# CamBienGiaToc.net
KiCad netlist of a schematic drawn in Altium Designer
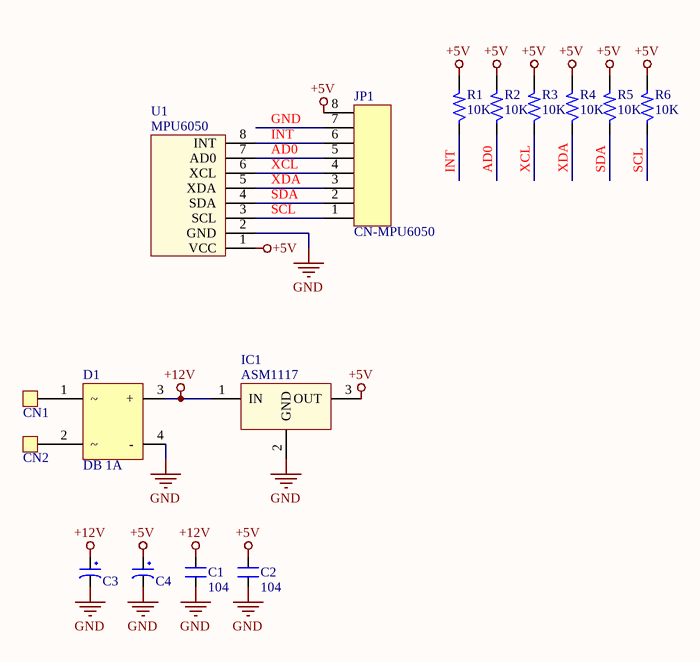
[diagram p0: CamBienGiaToc.SchDoc]

(export (version "E")
  (design (tool "Eeschema 10.0.6"))
  (components
    (comp (ref "C1")
      (value "104")
      (footprint "C-0805")
      (fields (field (name "DESIGNED BY") "VanDungEvn"))
      (libsource (lib "syhaunguyen") (part "CN"))
    )
    (comp (ref "C2")
      (value "104")
      (footprint "C-0805")
      (fields (field (name "DESIGNED BY") "VanDungEvn"))
      (libsource (lib "syhaunguyen") (part "CN"))
    )
    (comp (ref "C3")
      (value "10uF")
      (footprint "C-TANT-7343-31-CASEA")
      (description "Cap P  0,1uF < 22uF , 16 - 50V")
      (libsource (lib "syhaunguyen") (part "CP1"))
    )
    (comp (ref "C4")
      (value "10uF")
      (footprint "C-TANT-7343-31-CASEA")
      (description "Cap P  0,1uF < 22uF , 16 - 50V")
      (libsource (lib "syhaunguyen") (part "CP1"))
    )
    (comp (ref "CN1")
      (value "COCDONGM3")
      (footprint "M3")
      (libsource (lib "doAnTotNghiep2017Lib") (part "COCDONGM3"))
    )
    (comp (ref "CN2")
      (value "COCDONGM3")
      (footprint "M3")
      (libsource (lib "doAnTotNghiep2017Lib") (part "COCDONGM3"))
    )
    (comp (ref "D1")
      (value "DB 1A")
      (footprint "D-DB-1A-SMD")
      (libsource (lib "doAnTotNghiep2017Lib") (part "DB"))
    )
    (comp (ref "IC1")
      (value "ASM1117")
      (footprint "TO-252")
      (description "On ap +, from + 5 to + 24VDC")
      (libsource (lib "syhaunguyen") (part "LM78xx"))
    )
    (comp (ref "JP1")
      (value "CN-MPU6050")
      (footprint "JP8")
      (libsource (lib "doAnTotNghiep2017Lib") (part "JP8"))
    )
    (comp (ref "R1")
      (value "10K")
      (footprint "R-0805")
      (description "Resistor 1/4W")
      (libsource (lib "syhaunguyen") (part "R"))
    )
    (comp (ref "R2")
      (value "10K")
      (footprint "R-0805")
      (description "Resistor 1/4W")
      (libsource (lib "syhaunguyen") (part "R"))
    )
    (comp (ref "R3")
      (value "10K")
      (footprint "R-0805")
      (description "Resistor 1/4W")
      (libsource (lib "syhaunguyen") (part "R"))
    )
    (comp (ref "R4")
      (value "10K")
      (footprint "R-0805")
      (description "Resistor 1/4W")
      (libsource (lib "syhaunguyen") (part "R"))
    )
    (comp (ref "R5")
      (value "10K")
      (footprint "R-0805")
      (description "Resistor 1/4W")
      (libsource (lib "syhaunguyen") (part "R"))
    )
    (comp (ref "R6")
      (value "10K")
      (footprint "R-0805")
      (description "Resistor 1/4W")
      (libsource (lib "syhaunguyen") (part "R"))
    )
    (comp (ref "U1") (value "MPU6050") (libsource (lib "doAnTotNghiep2017Lib") (part "MPU6050")))
  )
  (nets
    (net (code "1") (name "+5V") (class "Default")
      (node (ref "C2") (pin "2") (pinfunction "2_2") (pintype "passive"))
      (node (ref "C4") (pin "1") (pinfunction "1_1") (pintype "passive"))
      (node (ref "IC1") (pin "3") (pinfunction "OUT_3") (pintype "passive"))
      (node (ref "JP1") (pin "8") (pinfunction "8_8") (pintype "passive"))
      (node (ref "R1") (pin "2") (pinfunction "2_2") (pintype "passive"))
      (node (ref "R2") (pin "2") (pinfunction "2_2") (pintype "passive"))
      (node (ref "R3") (pin "2") (pinfunction "2_2") (pintype "passive"))
      (node (ref "R4") (pin "2") (pinfunction "2_2") (pintype "passive"))
      (node (ref "R5") (pin "2") (pinfunction "2_2") (pintype "passive"))
      (node (ref "R6") (pin "2") (pinfunction "2_2") (pintype "passive"))
      (node (ref "U1") (pin "1") (pinfunction "VCC_1") (pintype "passive"))
    )
    (net (code "2") (name "+12V") (class "Default")
      (node (ref "C1") (pin "2") (pinfunction "2_2") (pintype "passive"))
      (node (ref "C3") (pin "1") (pinfunction "1_1") (pintype "passive"))
      (node (ref "D1") (pin "3") (pinfunction "+_3") (pintype "passive"))
      (node (ref "IC1") (pin "1") (pinfunction "IN_1") (pintype "passive"))
    )
    (net (code "3") (name "/AD0") (class "Default")
      (node (ref "JP1") (pin "5") (pinfunction "5_5") (pintype "passive"))
      (node (ref "R2") (pin "1") (pinfunction "1_1") (pintype "passive"))
      (node (ref "U1") (pin "7") (pinfunction "AD0_7") (pintype "passive"))
    )
    (net (code "4") (name "/INT") (class "Default")
      (node (ref "JP1") (pin "6") (pinfunction "6_6") (pintype "passive"))
      (node (ref "R1") (pin "1") (pinfunction "1_1") (pintype "passive"))
      (node (ref "U1") (pin "8") (pinfunction "INT_8") (pintype "passive"))
    )
    (net (code "5") (name "/SCL") (class "Default")
      (node (ref "JP1") (pin "1") (pinfunction "1_1") (pintype "passive"))
      (node (ref "R6") (pin "1") (pinfunction "1_1") (pintype "passive"))
      (node (ref "U1") (pin "3") (pinfunction "SCL_3") (pintype "passive"))
    )
    (net (code "6") (name "/SDA") (class "Default")
      (node (ref "JP1") (pin "2") (pinfunction "2_2") (pintype "passive"))
      (node (ref "R5") (pin "1") (pinfunction "1_1") (pintype "passive"))
      (node (ref "U1") (pin "4") (pinfunction "SDA_4") (pintype "passive"))
    )
    (net (code "7") (name "/XCL") (class "Default")
      (node (ref "JP1") (pin "4") (pinfunction "4_4") (pintype "passive"))
      (node (ref "R3") (pin "1") (pinfunction "1_1") (pintype "passive"))
      (node (ref "U1") (pin "6") (pinfunction "XCL_6") (pintype "passive"))
    )
    (net (code "8") (name "/XDA") (class "Default")
      (node (ref "JP1") (pin "3") (pinfunction "3_3") (pintype "passive"))
      (node (ref "R4") (pin "1") (pinfunction "1_1") (pintype "passive"))
      (node (ref "U1") (pin "5") (pinfunction "XDA_5") (pintype "passive"))
    )
    (net (code "9") (name "GND") (class "Default")
      (node (ref "C1") (pin "1") (pinfunction "1_1") (pintype "passive"))
      (node (ref "C2") (pin "1") (pinfunction "1_1") (pintype "passive"))
      (node (ref "C3") (pin "2") (pinfunction "2_2") (pintype "passive"))
      (node (ref "C4") (pin "2") (pinfunction "2_2") (pintype "passive"))
      (node (ref "D1") (pin "4") (pinfunction "-_4") (pintype "passive"))
      (node (ref "IC1") (pin "2") (pinfunction "GND_2") (pintype "passive"))
      (node (ref "JP1") (pin "7") (pinfunction "7_7") (pintype "passive"))
      (node (ref "U1") (pin "2") (pinfunction "GND_2") (pintype "passive"))
    )
    (net (code "10") (name "Net-(CN1-Pad1)") (class "Default")
      (node (ref "CN1") (pin "1") (pintype "passive"))
      (node (ref "D1") (pin "1") (pinfunction "~_1") (pintype "passive"))
    )
    (net (code "11") (name "Net-(CN2-Pad1)") (class "Default")
      (node (ref "CN2") (pin "1") (pintype "passive"))
      (node (ref "D1") (pin "2") (pinfunction "~_2") (pintype "passive"))
    )
  )
)
